# 8j-merge.net
KiCad netlist of a schematic drawn in EAGLE
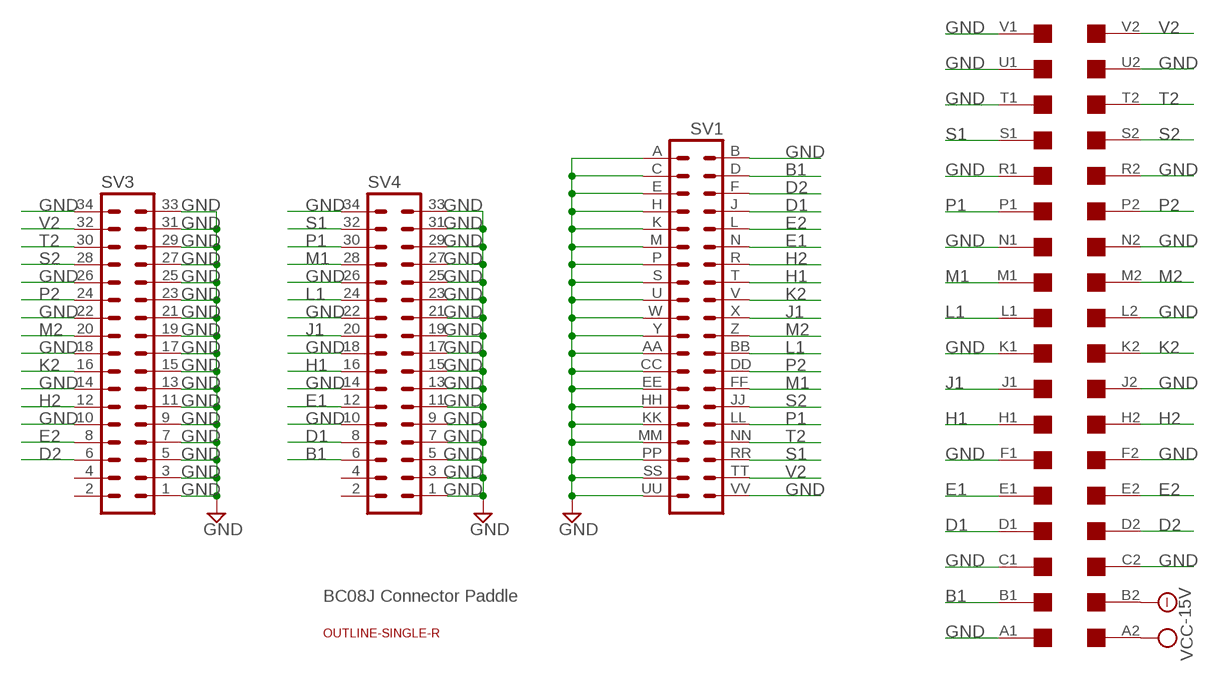
[diagram p0: schematic, sheet 1]

(export (version "E")
  (design (tool "Eeschema 10.0.6"))
  (components
    (comp (ref "SV1")
      (value "DEC40PINV")
      (footprint "eagle-import:DEC40PINV")
      (libsource (lib "eagle-import") (part "DEC40PINV"))
    )
    (comp (ref "SV3")
      (value "MA17-2")
      (footprint "eagle-import:MA17-2")
      (libsource (lib "eagle-import") (part "MA17-2"))
    )
    (comp (ref "SV4")
      (value "MA17-2")
      (footprint "eagle-import:MA17-2")
      (libsource (lib "eagle-import") (part "MA17-2"))
    )
    (comp (ref "U$1")
      (value "OUTLINE-SINGLE-R")
      (footprint "eagle-import:SINGLE-R")
      (libsource (lib "eagle-import") (part "OUTLINE-SINGLE-R"))
    )
    (comp (ref "U$2")
      (value "SINGLE")
      (footprint "eagle-import:EDGE-CON2")
      (libsource (lib "eagle-import") (part "SINGLE"))
    )
  )
  (nets
    (net (code "1") (name "-15V") (class "Default")
      (node (ref "U$2") (pin "B2") (pinfunction "1_B2") (pintype "bidirectional"))
    )
    (net (code "2") (name "/B1") (class "Default")
      (node (ref "SV1") (pin "D") (pinfunction "4_D") (pintype "bidirectional"))
      (node (ref "SV4") (pin "6") (pinfunction "6_6") (pintype "passive"))
      (node (ref "U$2") (pin "B1") (pinfunction "1_B1") (pintype "bidirectional"))
    )
    (net (code "3") (name "/D1") (class "Default")
      (node (ref "SV1") (pin "J") (pinfunction "8_J") (pintype "bidirectional"))
      (node (ref "SV4") (pin "8") (pinfunction "8_8") (pintype "passive"))
      (node (ref "U$2") (pin "D1") (pinfunction "1_D1") (pintype "bidirectional"))
    )
    (net (code "4") (name "/D2") (class "Default")
      (node (ref "SV1") (pin "F") (pinfunction "6_F") (pintype "bidirectional"))
      (node (ref "SV3") (pin "6") (pinfunction "6_6") (pintype "passive"))
      (node (ref "U$2") (pin "D2") (pinfunction "1_D2") (pintype "bidirectional"))
    )
    (net (code "5") (name "/E1") (class "Default")
      (node (ref "SV1") (pin "N") (pinfunction "12_N") (pintype "bidirectional"))
      (node (ref "SV4") (pin "12") (pinfunction "12_12") (pintype "passive"))
      (node (ref "U$2") (pin "E1") (pinfunction "1_E1") (pintype "bidirectional"))
    )
    (net (code "6") (name "/E2") (class "Default")
      (node (ref "SV1") (pin "L") (pinfunction "10_L") (pintype "bidirectional"))
      (node (ref "SV3") (pin "8") (pinfunction "8_8") (pintype "passive"))
      (node (ref "U$2") (pin "E2") (pinfunction "1_E2") (pintype "bidirectional"))
    )
    (net (code "7") (name "/H1") (class "Default")
      (node (ref "SV1") (pin "T") (pinfunction "16_T") (pintype "bidirectional"))
      (node (ref "SV4") (pin "16") (pinfunction "16_16") (pintype "passive"))
      (node (ref "U$2") (pin "H1") (pinfunction "1_H1") (pintype "bidirectional"))
    )
    (net (code "8") (name "/H2") (class "Default")
      (node (ref "SV1") (pin "R") (pinfunction "14_R") (pintype "bidirectional"))
      (node (ref "SV3") (pin "12") (pinfunction "12_12") (pintype "passive"))
      (node (ref "U$2") (pin "H2") (pinfunction "1_H2") (pintype "bidirectional"))
    )
    (net (code "9") (name "/J1") (class "Default")
      (node (ref "SV1") (pin "X") (pinfunction "20_X") (pintype "bidirectional"))
      (node (ref "SV4") (pin "20") (pinfunction "20_20") (pintype "passive"))
      (node (ref "U$2") (pin "J1") (pinfunction "1_J1") (pintype "bidirectional"))
    )
    (net (code "10") (name "/K2") (class "Default")
      (node (ref "SV1") (pin "V") (pinfunction "18_V") (pintype "bidirectional"))
      (node (ref "SV3") (pin "16") (pinfunction "16_16") (pintype "passive"))
      (node (ref "U$2") (pin "K2") (pinfunction "1_K2") (pintype "bidirectional"))
    )
    (net (code "11") (name "/L1") (class "Default")
      (node (ref "SV1") (pin "BB") (pinfunction "24_BB") (pintype "bidirectional"))
      (node (ref "SV4") (pin "24") (pinfunction "24_24") (pintype "passive"))
      (node (ref "U$2") (pin "L1") (pinfunction "1_L1") (pintype "bidirectional"))
    )
    (net (code "12") (name "/M1") (class "Default")
      (node (ref "SV1") (pin "FF") (pinfunction "28_FF") (pintype "bidirectional"))
      (node (ref "SV4") (pin "28") (pinfunction "28_28") (pintype "passive"))
      (node (ref "U$2") (pin "M1") (pinfunction "1_M1") (pintype "bidirectional"))
    )
    (net (code "13") (name "/M2") (class "Default")
      (node (ref "SV1") (pin "Z") (pinfunction "22_Z") (pintype "bidirectional"))
      (node (ref "SV3") (pin "20") (pinfunction "20_20") (pintype "passive"))
      (node (ref "U$2") (pin "M2") (pinfunction "1_M2") (pintype "bidirectional"))
    )
    (net (code "14") (name "/P1") (class "Default")
      (node (ref "SV1") (pin "LL") (pinfunction "32_LL") (pintype "bidirectional"))
      (node (ref "SV4") (pin "30") (pinfunction "30_30") (pintype "passive"))
      (node (ref "U$2") (pin "P1") (pinfunction "1_P1") (pintype "bidirectional"))
    )
    (net (code "15") (name "/P2") (class "Default")
      (node (ref "SV1") (pin "DD") (pinfunction "26_DD") (pintype "bidirectional"))
      (node (ref "SV3") (pin "24") (pinfunction "24_24") (pintype "passive"))
      (node (ref "U$2") (pin "P2") (pinfunction "1_P2") (pintype "bidirectional"))
    )
    (net (code "16") (name "/S1") (class "Default")
      (node (ref "SV1") (pin "RR") (pinfunction "36_RR") (pintype "bidirectional"))
      (node (ref "SV4") (pin "32") (pinfunction "32_32") (pintype "passive"))
      (node (ref "U$2") (pin "S1") (pinfunction "1_S1") (pintype "bidirectional"))
    )
    (net (code "17") (name "/S2") (class "Default")
      (node (ref "SV1") (pin "JJ") (pinfunction "30_JJ") (pintype "bidirectional"))
      (node (ref "SV3") (pin "28") (pinfunction "28_28") (pintype "passive"))
      (node (ref "U$2") (pin "S2") (pinfunction "1_S2") (pintype "bidirectional"))
    )
    (net (code "18") (name "/T2") (class "Default")
      (node (ref "SV1") (pin "NN") (pinfunction "34_NN") (pintype "bidirectional"))
      (node (ref "SV3") (pin "30") (pinfunction "30_30") (pintype "passive"))
      (node (ref "U$2") (pin "T2") (pinfunction "1_T2") (pintype "bidirectional"))
    )
    (net (code "19") (name "/V2") (class "Default")
      (node (ref "SV1") (pin "TT") (pinfunction "38_TT") (pintype "bidirectional"))
      (node (ref "SV3") (pin "32") (pinfunction "32_32") (pintype "passive"))
      (node (ref "U$2") (pin "V2") (pinfunction "1_V2") (pintype "bidirectional"))
    )
    (net (code "20") (name "GND") (class "Default")
      (node (ref "SV1") (pin "A") (pinfunction "1_A") (pintype "bidirectional"))
      (node (ref "SV1") (pin "AA") (pinfunction "23_AA") (pintype "bidirectional"))
      (node (ref "SV1") (pin "B") (pinfunction "2_B") (pintype "bidirectional"))
      (node (ref "SV1") (pin "C") (pinfunction "3_C") (pintype "bidirectional"))
      (node (ref "SV1") (pin "CC") (pinfunction "25_CC") (pintype "bidirectional"))
      (node (ref "SV1") (pin "E") (pinfunction "5_E") (pintype "bidirectional"))
      (node (ref "SV1") (pin "EE") (pinfunction "27_EE") (pintype "bidirectional"))
      (node (ref "SV1") (pin "H") (pinfunction "7_H") (pintype "bidirectional"))
      (node (ref "SV1") (pin "HH") (pinfunction "29_HH") (pintype "bidirectional"))
      (node (ref "SV1") (pin "K") (pinfunction "9_K") (pintype "bidirectional"))
      (node (ref "SV1") (pin "KK") (pinfunction "31_KK") (pintype "bidirectional"))
      (node (ref "SV1") (pin "M") (pinfunction "11_M") (pintype "bidirectional"))
      (node (ref "SV1") (pin "MM") (pinfunction "33_MM") (pintype "bidirectional"))
      (node (ref "SV1") (pin "P") (pinfunction "13_P") (pintype "bidirectional"))
      (node (ref "SV1") (pin "PP") (pinfunction "35_PP") (pintype "bidirectional"))
      (node (ref "SV1") (pin "S") (pinfunction "15_S") (pintype "bidirectional"))
      (node (ref "SV1") (pin "SS") (pinfunction "37_SS") (pintype "bidirectional"))
      (node (ref "SV1") (pin "U") (pinfunction "17_U") (pintype "bidirectional"))
      (node (ref "SV1") (pin "UU") (pinfunction "39_UU") (pintype "bidirectional"))
      (node (ref "SV1") (pin "VV") (pinfunction "40_VV") (pintype "bidirectional"))
      (node (ref "SV1") (pin "W") (pinfunction "19_W") (pintype "bidirectional"))
      (node (ref "SV1") (pin "Y") (pinfunction "21_Y") (pintype "bidirectional"))
      (node (ref "SV3") (pin "1") (pinfunction "1_1") (pintype "passive"))
      (node (ref "SV3") (pin "10") (pinfunction "10_10") (pintype "passive"))
      (node (ref "SV3") (pin "11") (pinfunction "11_11") (pintype "passive"))
      (node (ref "SV3") (pin "13") (pinfunction "13_13") (pintype "passive"))
      (node (ref "SV3") (pin "14") (pinfunction "14_14") (pintype "passive"))
      (node (ref "SV3") (pin "15") (pinfunction "15_15") (pintype "passive"))
      (node (ref "SV3") (pin "17") (pinfunction "17_17") (pintype "passive"))
      (node (ref "SV3") (pin "18") (pinfunction "18_18") (pintype "passive"))
      (node (ref "SV3") (pin "19") (pinfunction "19_19") (pintype "passive"))
      (node (ref "SV3") (pin "21") (pinfunction "21_21") (pintype "passive"))
      (node (ref "SV3") (pin "22") (pinfunction "22_22") (pintype "passive"))
      (node (ref "SV3") (pin "23") (pinfunction "23_23") (pintype "passive"))
      (node (ref "SV3") (pin "25") (pinfunction "25_25") (pintype "passive"))
      (node (ref "SV3") (pin "26") (pinfunction "26_26") (pintype "passive"))
      (node (ref "SV3") (pin "27") (pinfunction "27_27") (pintype "passive"))
      (node (ref "SV3") (pin "29") (pinfunction "29_29") (pintype "passive"))
      (node (ref "SV3") (pin "3") (pinfunction "3_3") (pintype "passive"))
      (node (ref "SV3") (pin "31") (pinfunction "31_31") (pintype "passive"))
      (node (ref "SV3") (pin "33") (pinfunction "33_33") (pintype "passive"))
      (node (ref "SV3") (pin "34") (pinfunction "34_34") (pintype "passive"))
      (node (ref "SV3") (pin "5") (pinfunction "5_5") (pintype "passive"))
      (node (ref "SV3") (pin "7") (pinfunction "7_7") (pintype "passive"))
      (node (ref "SV3") (pin "9") (pinfunction "9_9") (pintype "passive"))
      (node (ref "SV4") (pin "1") (pinfunction "1_1") (pintype "passive"))
      (node (ref "SV4") (pin "10") (pinfunction "10_10") (pintype "passive"))
      (node (ref "SV4") (pin "11") (pinfunction "11_11") (pintype "passive"))
      (node (ref "SV4") (pin "13") (pinfunction "13_13") (pintype "passive"))
      (node (ref "SV4") (pin "14") (pinfunction "14_14") (pintype "passive"))
      (node (ref "SV4") (pin "15") (pinfunction "15_15") (pintype "passive"))
      (node (ref "SV4") (pin "17") (pinfunction "17_17") (pintype "passive"))
      (node (ref "SV4") (pin "18") (pinfunction "18_18") (pintype "passive"))
      (node (ref "SV4") (pin "19") (pinfunction "19_19") (pintype "passive"))
      (node (ref "SV4") (pin "21") (pinfunction "21_21") (pintype "passive"))
      (node (ref "SV4") (pin "22") (pinfunction "22_22") (pintype "passive"))
      (node (ref "SV4") (pin "23") (pinfunction "23_23") (pintype "passive"))
      (node (ref "SV4") (pin "25") (pinfunction "25_25") (pintype "passive"))
      (node (ref "SV4") (pin "26") (pinfunction "26_26") (pintype "passive"))
      (node (ref "SV4") (pin "27") (pinfunction "27_27") (pintype "passive"))
      (node (ref "SV4") (pin "29") (pinfunction "29_29") (pintype "passive"))
      (node (ref "SV4") (pin "3") (pinfunction "3_3") (pintype "passive"))
      (node (ref "SV4") (pin "31") (pinfunction "31_31") (pintype "passive"))
      (node (ref "SV4") (pin "33") (pinfunction "33_33") (pintype "passive"))
      (node (ref "SV4") (pin "34") (pinfunction "34_34") (pintype "passive"))
      (node (ref "SV4") (pin "5") (pinfunction "5_5") (pintype "passive"))
      (node (ref "SV4") (pin "7") (pinfunction "7_7") (pintype "passive"))
      (node (ref "SV4") (pin "9") (pinfunction "9_9") (pintype "passive"))
      (node (ref "U$2") (pin "A1") (pinfunction "1_A1") (pintype "bidirectional"))
      (node (ref "U$2") (pin "C1") (pinfunction "1_C1") (pintype "bidirectional"))
      (node (ref "U$2") (pin "C2") (pinfunction "1_C2") (pintype "bidirectional"))
      (node (ref "U$2") (pin "F1") (pinfunction "1_F1") (pintype "bidirectional"))
      (node (ref "U$2") (pin "F2") (pinfunction "1_F2") (pintype "bidirectional"))
      (node (ref "U$2") (pin "J2") (pinfunction "1_J2") (pintype "bidirectional"))
      (node (ref "U$2") (pin "K1") (pinfunction "1_K1") (pintype "bidirectional"))
      (node (ref "U$2") (pin "L2") (pinfunction "1_L2") (pintype "bidirectional"))
      (node (ref "U$2") (pin "N1") (pinfunction "1_N1") (pintype "bidirectional"))
      (node (ref "U$2") (pin "N2") (pinfunction "1_N2") (pintype "bidirectional"))
      (node (ref "U$2") (pin "R1") (pinfunction "1_R1") (pintype "bidirectional"))
      (node (ref "U$2") (pin "R2") (pinfunction "1_R2") (pintype "bidirectional"))
      (node (ref "U$2") (pin "T1") (pinfunction "1_T1") (pintype "bidirectional"))
      (node (ref "U$2") (pin "U1") (pinfunction "1_U1") (pintype "bidirectional"))
      (node (ref "U$2") (pin "U2") (pinfunction "1_U2") (pintype "bidirectional"))
      (node (ref "U$2") (pin "V1") (pinfunction "1_V1") (pintype "bidirectional"))
    )
    (net (code "21") (name "VCC") (class "Default")
      (node (ref "U$2") (pin "A2") (pinfunction "1_A2") (pintype "bidirectional"))
    )
    (net (code "22") (name "unconnected-(SV3-Pad2)") (class "Default")
      (node (ref "SV3") (pin "2") (pinfunction "2_2") (pintype "passive"))
    )
    (net (code "23") (name "unconnected-(SV3-Pad4)") (class "Default")
      (node (ref "SV3") (pin "4") (pinfunction "4_4") (pintype "passive"))
    )
    (net (code "24") (name "unconnected-(SV4-Pad2)") (class "Default")
      (node (ref "SV4") (pin "2") (pinfunction "2_2") (pintype "passive"))
    )
    (net (code "25") (name "unconnected-(SV4-Pad4)") (class "Default")
      (node (ref "SV4") (pin "4") (pinfunction "4_4") (pintype "passive"))
    )
  )
)
